# supply.net
KiCad netlist of a schematic drawn in Altium Designer
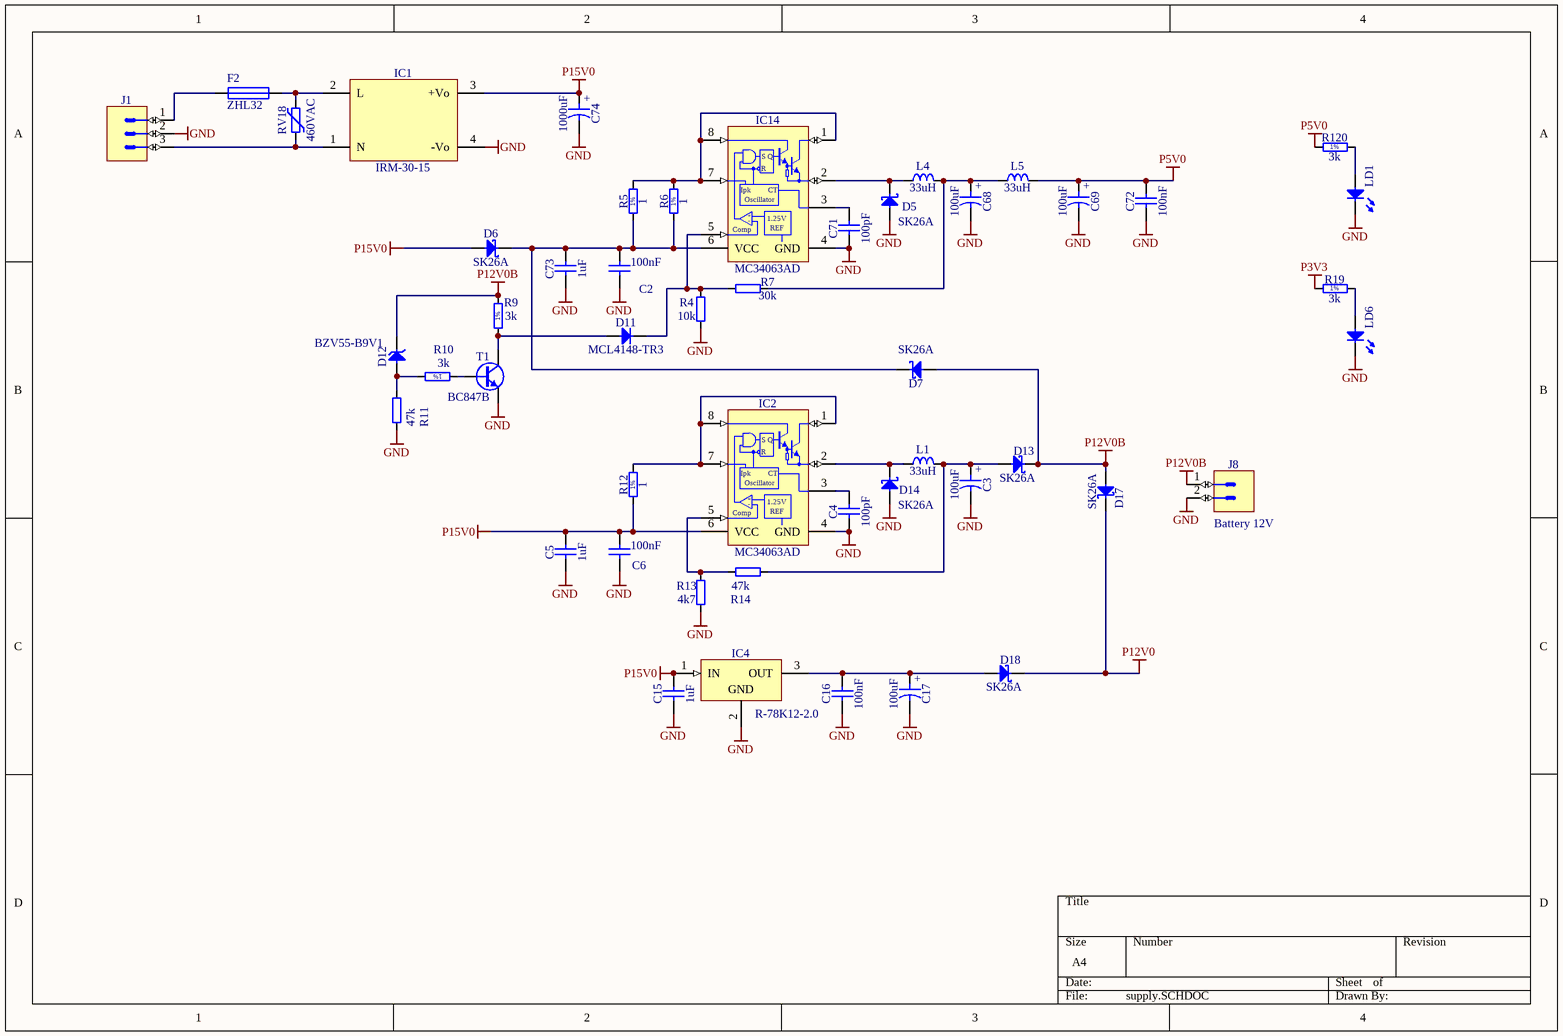
[diagram p0: supply.SCHDOC]

(export (version "E")
  (design (tool "Eeschema 10.0.6"))
  (components
    (comp (ref "C2")
      (value "100nF")
      (footprint "CAPC1608X87N")
      (description "Non-polarised capacitor")
      (fields
        (field (name "PART NUMBER") "CC0603_100NF_50V_10%_X7R")
        (field (name "VOLTAGE") "50V")
        (field (name "AUTHOR") "CERN DEM JLC")
      )
      (libsource (lib "Capacitors") (part "Capacitor - non polarized"))
    )
    (comp (ref "C3")
      (value "100uF")
      (footprint "CAPAE660X540N")
      (description "Polarised capacitor")
      (fields
        (field (name "PART NUMBER") "CAE660-540_100UF_16V_20%")
        (field (name "VOLTAGE") "16V")
        (field (name "AUTHOR") "CERN DEM JLC")
      )
      (libsource (lib "Capacitors") (part "Capacitor - polarized"))
    )
    (comp (ref "C4")
      (value "100pF")
      (footprint "CAPC1608X87N")
      (description "Non-polarised capacitor")
      (fields
        (field (name "PART NUMBER") "CC0603_100PF_50V_10%_X7R")
        (field (name "VOLTAGE") "50V")
        (field (name "AUTHOR") "CERN DEM JLC")
      )
      (libsource (lib "Capacitors") (part "Capacitor - non polarized"))
    )
    (comp (ref "C5")
      (value "1uF")
      (footprint "CAPC1608X87N")
      (description "Non-polarised capacitor")
      (fields
        (field (name "PART NUMBER") "CC0603_1UF_25V_10%_X7R")
        (field (name "VOLTAGE") "25V")
        (field (name "AUTHOR") "CERN DEM JLC")
      )
      (libsource (lib "Capacitors") (part "Capacitor - non polarized"))
    )
    (comp (ref "C6")
      (value "100nF")
      (footprint "CAPC1608X87N")
      (description "Non-polarised capacitor")
      (fields
        (field (name "PART NUMBER") "CC0603_100NF_50V_10%_X7R")
        (field (name "VOLTAGE") "50V")
        (field (name "AUTHOR") "CERN DEM JLC")
      )
      (libsource (lib "Capacitors") (part "Capacitor - non polarized"))
    )
    (comp (ref "C15")
      (value "1uF")
      (footprint "CAPC1608X87N")
      (description "Non-polarised capacitor")
      (fields
        (field (name "PART NUMBER") "CC0603_1UF_25V_10%_X7R")
        (field (name "VOLTAGE") "25V")
        (field (name "AUTHOR") "CERN DEM JLC")
      )
      (libsource (lib "Capacitors") (part "Capacitor - non polarized"))
    )
    (comp (ref "C16")
      (value "100nF")
      (footprint "CAPC1608X87N")
      (description "Non-polarised capacitor")
      (fields
        (field (name "PART NUMBER") "CC0603_100NF_50V_10%_X7R")
        (field (name "VOLTAGE") "50V")
        (field (name "AUTHOR") "CERN DEM JLC")
      )
      (libsource (lib "Capacitors") (part "Capacitor - non polarized"))
    )
    (comp (ref "C17")
      (value "100uF")
      (footprint "CAPAE660X540N")
      (description "Polarised capacitor")
      (fields
        (field (name "PART NUMBER") "CAE660-540_100UF_16V_20%")
        (field (name "VOLTAGE") "16V")
        (field (name "AUTHOR") "CERN DEM JLC")
      )
      (libsource (lib "Capacitors") (part "Capacitor - polarized"))
    )
    (comp (ref "C68")
      (value "100uF")
      (footprint "CAPAE660X540N")
      (description "Polarised capacitor")
      (fields
        (field (name "PART NUMBER") "CAE660-540_100UF_16V_20%")
        (field (name "VOLTAGE") "16V")
        (field (name "AUTHOR") "CERN DEM JLC")
      )
      (libsource (lib "Capacitors") (part "Capacitor - polarized"))
    )
    (comp (ref "C69")
      (value "100uF")
      (footprint "CAPAE660X540N")
      (description "Polarised capacitor")
      (fields
        (field (name "PART NUMBER") "CAE660-540_100UF_16V_20%")
        (field (name "VOLTAGE") "16V")
        (field (name "AUTHOR") "CERN DEM JLC")
      )
      (libsource (lib "Capacitors") (part "Capacitor - polarized"))
    )
    (comp (ref "C71")
      (value "100pF")
      (footprint "CAPC1608X87N")
      (description "Non-polarised capacitor")
      (fields
        (field (name "PART NUMBER") "CC0603_100PF_50V_10%_X7R")
        (field (name "VOLTAGE") "50V")
        (field (name "AUTHOR") "CERN DEM JLC")
      )
      (libsource (lib "Capacitors") (part "Capacitor - non polarized"))
    )
    (comp (ref "C72")
      (value "100nF")
      (footprint "CAPC1608X87N")
      (description "Non-polarised capacitor")
      (fields
        (field (name "PART NUMBER") "CC0603_100NF_50V_10%_X7R")
        (field (name "VOLTAGE") "50V")
        (field (name "AUTHOR") "CERN DEM JLC")
      )
      (libsource (lib "Capacitors") (part "Capacitor - non polarized"))
    )
    (comp (ref "C73")
      (value "1uF")
      (footprint "CAPC1608X87N")
      (description "Non-polarised capacitor")
      (fields
        (field (name "PART NUMBER") "CC0603_1UF_25V_10%_X7R")
        (field (name "VOLTAGE") "25V")
        (field (name "AUTHOR") "CERN DEM JLC")
      )
      (libsource (lib "Capacitors") (part "Capacitor - non polarized"))
    )
    (comp (ref "C74")
      (value "1000uF")
      (footprint "CAPPR500-1050X2200")
      (description "Polarised capacitor")
      (fields
        (field (name "PART NUMBER") "CAER_1000UF_25V_20%_VISHAY_MAL203856102E3")
        (field (name "VOLTAGE") "25V")
        (field (name "AUTHOR") "CERN DEM JLC")
      )
      (libsource (lib "Capacitors") (part "Capacitor - polarized"))
    )
    (comp (ref "D5")
      (value "SK26A")
      (footprint "DIOM5126X265N")
      (description "Schottky Diode")
      (fields
        (field (name "VOLTAGE") "60V")
        (field (name "POWER") "2A")
        (field (name "AUTHOR") "CERN DEM JMW")
      )
      (libsource (lib "ICs And Semiconductors") (part "Diode Schottky"))
    )
    (comp (ref "D6")
      (value "SK26A")
      (footprint "DIOM5126X265N")
      (description "Schottky Diode")
      (fields
        (field (name "VOLTAGE") "60V")
        (field (name "POWER") "2A")
        (field (name "AUTHOR") "CERN DEM JMW")
      )
      (libsource (lib "ICs And Semiconductors") (part "Diode Schottky"))
    )
    (comp (ref "D7")
      (value "SK26A")
      (footprint "DIOM5126X265N")
      (description "Schottky Diode")
      (fields
        (field (name "VOLTAGE") "60V")
        (field (name "POWER") "2A")
        (field (name "AUTHOR") "CERN DEM JMW")
      )
      (libsource (lib "ICs And Semiconductors") (part "Diode Schottky"))
    )
    (comp (ref "D11")
      (value "MCL4148-TR3")
      (footprint "DIOMELF1911N")
      (description "Diode")
      (fields
        (field (name "VOLTAGE") "75V")
        (field (name "POWER") "200mA")
        (field (name "AUTHOR") "CERN DEM JLC")
      )
      (libsource (lib "ICs And Semiconductors") (part "Diode"))
    )
    (comp (ref "D12")
      (value "BZV55-B9V1")
      (footprint "DIOMELF3515N")
      (description "Zener Diode")
      (fields
        (field (name "VOLTAGE") "9V1")
        (field (name "POWER") "500mW")
        (field (name "AUTHOR") "CERN DEM JLC")
      )
      (libsource (lib "ICs And Semiconductors") (part "Diode Zener"))
    )
    (comp (ref "D13")
      (value "SK26A")
      (footprint "DIOM5126X265N")
      (description "Schottky Diode")
      (fields
        (field (name "VOLTAGE") "60V")
        (field (name "POWER") "2A")
        (field (name "AUTHOR") "CERN DEM JMW")
      )
      (libsource (lib "ICs And Semiconductors") (part "Diode Schottky"))
    )
    (comp (ref "D14")
      (value "SK26A")
      (footprint "DIOM5126X265N")
      (description "Schottky Diode")
      (fields
        (field (name "VOLTAGE") "60V")
        (field (name "POWER") "2A")
        (field (name "AUTHOR") "CERN DEM JMW")
      )
      (libsource (lib "ICs And Semiconductors") (part "Diode Schottky"))
    )
    (comp (ref "D17")
      (value "SK26A")
      (footprint "DIOM5126X265N")
      (description "Schottky Diode")
      (fields
        (field (name "VOLTAGE") "60V")
        (field (name "POWER") "2A")
        (field (name "AUTHOR") "CERN DEM JMW")
      )
      (libsource (lib "ICs And Semiconductors") (part "Diode Schottky"))
    )
    (comp (ref "D18")
      (value "SK26A")
      (footprint "DIOM5126X265N")
      (description "Schottky Diode")
      (fields
        (field (name "VOLTAGE") "60V")
        (field (name "POWER") "2A")
        (field (name "AUTHOR") "CERN DEM JMW")
      )
      (libsource (lib "ICs And Semiconductors") (part "Diode Schottky"))
    )
    (comp (ref "F2")
      (value "ZHL32")
      (footprint "library:fuse_ZHL32")
      (description "Fuse")
      (libsource (lib "LIBRARY_SCH") (part "FUSE"))
    )
    (comp (ref "IC1")
      (value "IRM-30-15")
      (footprint "library-modules:PWS_MEANWELL_IRM-30")
      (description "Power Supply")
      (fields (field (name "MANUFACTURER") "MEAN WELL") (field (name "AUTHOR") "GK"))
      (libsource (lib "Regulators_SMPS") (part "AC_DC_IRM-30-15"))
    )
    (comp (ref "IC2")
      (value "MC34063AD")
      (footprint "SOIC127P600X175-8N")
      (description "3V to 40V 1.5A Peak Boost/Buck/Inverting Switching Regulator")
      (fields (field (name "MANUFACTURER") "TEXAS INSTRUMENTS") (field (name "AUTHOR") "CERN DEM JLC"))
      (libsource (lib "ICs And Semiconductors") (part "MC34063A"))
    )
    (comp (ref "IC4")
      (value "R-78K12-2.0")
      (footprint "DCDC_RECOM_R-78C")
      (description "15-42VDC to 12VDC, Iout (max) 1A, DC-DC Converter")
      (fields (field (name "MANUFACTURER") "RECOM") (field (name "AUTHOR") "CERN DEM BC"))
      (libsource (lib "ICs And Semiconductors") (part "DCDC_RECOM_R-78C"))
    )
    (comp (ref "IC14")
      (value "MC34063AD")
      (footprint "SOIC127P600X175-8N")
      (description "3V to 40V 1.5A Peak Boost/Buck/Inverting Switching Regulator")
      (fields (field (name "MANUFACTURER") "TEXAS INSTRUMENTS") (field (name "AUTHOR") "CERN DEM JLC"))
      (libsource (lib "ICs And Semiconductors") (part "MC34063A"))
    )
    (comp (ref "J1")
      (value "~")
      (footprint "PHOENIX_1757255")
      (description "Connector 3 Male")
      (fields
        (field (name "PART NUMBER") "PHOENIX_1757255")
        (field (name "MANUFACTURER") "PHOENIX CONTACT")
        (field (name "AUTHOR") "CERN DEM JLC")
      )
      (libsource (lib "Connectors") (part "Connector 3 Male"))
    )
    (comp (ref "J8")
      (value "~")
      (footprint "PHOENIX_1803277")
      (description "Connector 2 Male")
      (fields
        (field (name "PART NUMBER") "PHOENIX_1803277")
        (field (name "MANUFACTURER") "PHOENIX CONTACT")
        (field (name "AUTHOR") "CERN DEM JLC")
      )
      (libsource (lib "Connectors") (part "Connector 2 Male"))
    )
    (comp (ref "L1")
      (value "33uH")
      (footprint "IND_BOURNS_SRP1038A")
      (description "Inductor")
      (fields
        (field (name "PART NUMBER") "IND_33UH_20%_BOURNS_SRP1038A")
        (field (name "POWER") "3.5A")
        (field (name "AUTHOR") "CERN DEM HF")
      )
      (libsource (lib "Inductors & Transformers") (part "Inductor"))
    )
    (comp (ref "L4")
      (value "33uH")
      (footprint "IND_BOURNS_SRP1038A")
      (description "Inductor")
      (fields
        (field (name "PART NUMBER") "IND_33UH_20%_BOURNS_SRP1038A")
        (field (name "POWER") "3.5A")
        (field (name "AUTHOR") "CERN DEM HF")
      )
      (libsource (lib "Inductors & Transformers") (part "Inductor"))
    )
    (comp (ref "L5")
      (value "33uH")
      (footprint "IND_BOURNS_SRP1038A")
      (description "Inductor")
      (fields
        (field (name "PART NUMBER") "IND_33UH_20%_BOURNS_SRP1038A")
        (field (name "POWER") "3.5A")
        (field (name "AUTHOR") "CERN DEM HF")
      )
      (libsource (lib "Inductors & Transformers") (part "Inductor"))
    )
    (comp (ref "LD1")
      (value "Green")
      (footprint "LED_KINGBRIGHT_KP-1608CGCK")
      (description "LED Green 1C 2A")
      (fields
        (field (name "PART NUMBER") "LED_KINGBRIGHT_KP-1608CGCK")
        (field (name "MANUFACTURER") "KINGBRIGHT")
        (field (name "AUTHOR") "CERN DEM HF")
      )
      (libsource (lib "ICs And Semiconductors") (part "LED Green 1C 2A"))
    )
    (comp (ref "LD6")
      (value "Green")
      (footprint "LED_KINGBRIGHT_KP-1608CGCK")
      (description "LED Green 1C 2A")
      (fields
        (field (name "PART NUMBER") "LED_KINGBRIGHT_KP-1608CGCK")
        (field (name "MANUFACTURER") "KINGBRIGHT")
        (field (name "AUTHOR") "CERN DEM HF")
      )
      (libsource (lib "ICs And Semiconductors") (part "LED Green 1C 2A"))
    )
    (comp (ref "R4")
      (value "10k")
      (footprint "RESC1608X55N")
      (description "Resistor - 1%")
      (fields
        (field (name "PART NUMBER") "R0603_10K_1%_0.1W_100PPM")
        (field (name "POWER") "0.1W")
        (field (name "AUTHOR") "CERN DEM JLC")
      )
      (libsource (lib "Resistors") (part "Resistor - 1%"))
    )
    (comp (ref "R5")
      (value "1")
      (footprint "RESC1608X55N")
      (description "Resistor - 1%")
      (fields
        (field (name "PART NUMBER") "R0603_1R_1%_0.1W_200PPM")
        (field (name "POWER") "0.1W")
        (field (name "AUTHOR") "CERN DEM JLC")
      )
      (libsource (lib "Resistors") (part "Resistor - 1%"))
    )
    (comp (ref "R6")
      (value "1")
      (footprint "RESC1608X55N")
      (description "Resistor - 1%")
      (fields
        (field (name "PART NUMBER") "R0603_1R_1%_0.1W_200PPM")
        (field (name "POWER") "0.1W")
        (field (name "AUTHOR") "CERN DEM JLC")
      )
      (libsource (lib "Resistors") (part "Resistor - 1%"))
    )
    (comp (ref "R7")
      (value "30k")
      (footprint "RESC1608X55N")
      (description "Resistor - 1%")
      (fields
        (field (name "PART NUMBER") "R0603_30K_1%_0.1W_100PPM")
        (field (name "POWER") "0.1W")
        (field (name "AUTHOR") "CERN DEM JLC")
      )
      (libsource (lib "Resistors") (part "Resistor - 1%"))
    )
    (comp (ref "R9")
      (value "3k")
      (footprint "RESC1608X55N")
      (description "Resistor - 1%")
      (fields
        (field (name "PART NUMBER") "R0603_3K_1%_0.1W_100PPM")
        (field (name "POWER") "0.1W")
        (field (name "AUTHOR") "CERN DEM JLC")
      )
      (libsource (lib "Resistors") (part "Resistor - 1%"))
    )
    (comp (ref "R10")
      (value "3k")
      (footprint "RESC1608X55N")
      (description "Resistor - 1%")
      (fields
        (field (name "PART NUMBER") "R0603_3K_1%_0.1W_100PPM")
        (field (name "POWER") "0.1W")
        (field (name "AUTHOR") "CERN DEM JLC")
      )
      (libsource (lib "Resistors") (part "Resistor - 1%"))
    )
    (comp (ref "R11")
      (value "47k")
      (footprint "RESC1608X55N")
      (description "Resistor - 1%")
      (fields
        (field (name "PART NUMBER") "R0603_47K_1%_0.1W_100PPM")
        (field (name "POWER") "0.1W")
        (field (name "AUTHOR") "CERN DEM JLC")
      )
      (libsource (lib "Resistors") (part "Resistor - 1%"))
    )
    (comp (ref "R12")
      (value "1")
      (footprint "RESC1608X55N")
      (description "Resistor - 1%")
      (fields
        (field (name "PART NUMBER") "R0603_1R_1%_0.1W_200PPM")
        (field (name "POWER") "0.1W")
        (field (name "AUTHOR") "CERN DEM JLC")
      )
      (libsource (lib "Resistors") (part "Resistor - 1%"))
    )
    (comp (ref "R13")
      (value "4k7")
      (footprint "RESC1608X55N")
      (description "Resistor - 1%")
      (fields
        (field (name "PART NUMBER") "R0603_4K7_1%_0.1W_100PPM")
        (field (name "POWER") "0.1W")
        (field (name "AUTHOR") "CERN DEM JLC")
      )
      (libsource (lib "Resistors") (part "Resistor - 1%"))
    )
    (comp (ref "R14")
      (value "47k")
      (footprint "RESC1608X55N")
      (description "Resistor - 1%")
      (fields
        (field (name "PART NUMBER") "R0603_47K_1%_0.1W_100PPM")
        (field (name "POWER") "0.1W")
        (field (name "AUTHOR") "CERN DEM JLC")
      )
      (libsource (lib "Resistors") (part "Resistor - 1%"))
    )
    (comp (ref "R19")
      (value "3k")
      (footprint "RESC1608X55N")
      (description "Resistor - 1%")
      (fields
        (field (name "PART NUMBER") "R0603_3K_1%_0.1W_100PPM")
        (field (name "POWER") "0.1W")
        (field (name "AUTHOR") "CERN DEM JLC")
      )
      (libsource (lib "Resistors") (part "Resistor - 1%"))
    )
    (comp (ref "R120")
      (value "3k")
      (footprint "RESC1608X55N")
      (description "Resistor - 1%")
      (fields
        (field (name "PART NUMBER") "R0603_3K_1%_0.1W_100PPM")
        (field (name "POWER") "0.1W")
        (field (name "AUTHOR") "CERN DEM JLC")
      )
      (libsource (lib "Resistors") (part "Resistor - 1%"))
    )
    (comp (ref "RV18")
      (value "460VAC")
      (footprint "VAR_EPCOS_B72210S0461K101")
      (description "Varistor")
      (fields
        (field (name "PART NUMBER") "VAR_EPCOS_B72210S0461K101")
        (field (name "POWER") "0.4W")
        (field (name "AUTHOR") "CERN DEM JLC")
      )
      (libsource (lib "Resistors") (part "Varistor"))
    )
    (comp (ref "T1")
      (value "BC847B")
      (footprint "SOT95P230X110-3N")
      (description "NPN Transistor")
      (fields (field (name "MANUFACTURER") "NXP SEMICONDUCTORS") (field (name "AUTHOR") "CERN DEM JLC"))
      (libsource (lib "ICs And Semiconductors") (part "NPN B1 E2 C3"))
    )
  )
  (nets
    (net (code "1") (name "GND") (class "Default")
      (node (ref "C15") (pin "1") (pinfunction "1_1") (pintype "passive"))
      (node (ref "C16") (pin "1") (pinfunction "1_1") (pintype "passive"))
      (node (ref "C17") (pin "2") (pinfunction "2_2") (pintype "passive"))
      (node (ref "C2") (pin "1") (pinfunction "1_1") (pintype "passive"))
      (node (ref "C3") (pin "2") (pinfunction "2_2") (pintype "passive"))
      (node (ref "C4") (pin "1") (pinfunction "1_1") (pintype "passive"))
      (node (ref "C5") (pin "1") (pinfunction "1_1") (pintype "passive"))
      (node (ref "C6") (pin "1") (pinfunction "1_1") (pintype "passive"))
      (node (ref "C68") (pin "2") (pinfunction "2_2") (pintype "passive"))
      (node (ref "C69") (pin "2") (pinfunction "2_2") (pintype "passive"))
      (node (ref "C71") (pin "1") (pinfunction "1_1") (pintype "passive"))
      (node (ref "C72") (pin "1") (pinfunction "1_1") (pintype "passive"))
      (node (ref "C73") (pin "1") (pinfunction "1_1") (pintype "passive"))
      (node (ref "C74") (pin "2") (pinfunction "2_2") (pintype "passive"))
      (node (ref "D14") (pin "2") (pinfunction "A_2") (pintype "passive"))
      (node (ref "D5") (pin "2") (pinfunction "A_2") (pintype "passive"))
      (node (ref "IC1") (pin "4") (pinfunction "-Vo_4") (pintype "power_in"))
      (node (ref "IC14") (pin "4") (pinfunction "GND_4") (pintype "power_in"))
      (node (ref "IC2") (pin "4") (pinfunction "GND_4") (pintype "power_in"))
      (node (ref "IC4") (pin "2") (pinfunction "GND_2") (pintype "power_in"))
      (node (ref "J1") (pin "2") (pinfunction "2_2") (pintype "bidirectional"))
      (node (ref "J8") (pin "2") (pinfunction "2_2") (pintype "bidirectional"))
      (node (ref "LD1") (pin "1") (pinfunction "C_1") (pintype "passive"))
      (node (ref "LD6") (pin "1") (pinfunction "C_1") (pintype "passive"))
      (node (ref "R11") (pin "1") (pinfunction "1_1") (pintype "passive"))
      (node (ref "R13") (pin "1") (pinfunction "1_1") (pintype "passive"))
      (node (ref "R4") (pin "1") (pinfunction "1_1") (pintype "passive"))
      (node (ref "T1") (pin "2") (pinfunction "E_2") (pintype "passive"))
    )
    (net (code "2") (name "Net-(C68-Pad1)") (class "Default")
      (node (ref "C68") (pin "1") (pinfunction "1_1") (pintype "passive"))
      (node (ref "L4") (pin "2") (pinfunction "2_2") (pintype "passive"))
      (node (ref "L5") (pin "1") (pinfunction "1_1") (pintype "passive"))
      (node (ref "R7") (pin "2") (pinfunction "2_2") (pintype "passive"))
    )
    (net (code "3") (name "Net-(D5-C)") (class "Default")
      (node (ref "D5") (pin "1") (pinfunction "C_1") (pintype "passive"))
      (node (ref "IC14") (pin "2") (pinfunction "SWE_2") (pintype "bidirectional"))
      (node (ref "L4") (pin "1") (pinfunction "1_1") (pintype "passive"))
    )
    (net (code "4") (name "Net-(D6-C)") (class "Default")
      (node (ref "C2") (pin "2") (pinfunction "2_2") (pintype "passive"))
      (node (ref "C73") (pin "2") (pinfunction "2_2") (pintype "passive"))
      (node (ref "D6") (pin "1") (pinfunction "C_1") (pintype "passive"))
      (node (ref "D7") (pin "1") (pinfunction "C_1") (pintype "passive"))
      (node (ref "IC14") (pin "6") (pinfunction "VCC_6") (pintype "power_in"))
      (node (ref "R5") (pin "1") (pinfunction "1_1") (pintype "passive"))
      (node (ref "R6") (pin "1") (pinfunction "1_1") (pintype "passive"))
    )
    (net (code "5") (name "Net-(D11-A)") (class "Default")
      (node (ref "D11") (pin "2") (pinfunction "A_2") (pintype "passive"))
      (node (ref "R9") (pin "1") (pinfunction "1_1") (pintype "passive"))
      (node (ref "T1") (pin "3") (pinfunction "C_3") (pintype "passive"))
    )
    (net (code "6") (name "Net-(D11-C)") (class "Default")
      (node (ref "D11") (pin "1") (pinfunction "C_1") (pintype "passive"))
      (node (ref "IC14") (pin "5") (pinfunction "COMP_5") (pintype "input"))
      (node (ref "R4") (pin "2") (pinfunction "2_2") (pintype "passive"))
      (node (ref "R7") (pin "1") (pinfunction "1_1") (pintype "passive"))
    )
    (net (code "7") (name "Net-(D12-A)") (class "Default")
      (node (ref "D12") (pin "2") (pinfunction "A_2") (pintype "passive"))
      (node (ref "R10") (pin "2") (pinfunction "2_2") (pintype "passive"))
      (node (ref "R11") (pin "2") (pinfunction "2_2") (pintype "passive"))
    )
    (net (code "8") (name "Net-(D13-A)") (class "Default")
      (node (ref "C3") (pin "1") (pinfunction "1_1") (pintype "passive"))
      (node (ref "D13") (pin "2") (pinfunction "A_2") (pintype "passive"))
      (node (ref "L1") (pin "2") (pinfunction "2_2") (pintype "passive"))
      (node (ref "R14") (pin "2") (pinfunction "2_2") (pintype "passive"))
    )
    (net (code "9") (name "Net-(D14-C)") (class "Default")
      (node (ref "D14") (pin "1") (pinfunction "C_1") (pintype "passive"))
      (node (ref "IC2") (pin "2") (pinfunction "SWE_2") (pintype "bidirectional"))
      (node (ref "L1") (pin "1") (pinfunction "1_1") (pintype "passive"))
    )
    (net (code "10") (name "Net-(D18-A)") (class "Default")
      (node (ref "C16") (pin "2") (pinfunction "2_2") (pintype "passive"))
      (node (ref "C17") (pin "1") (pinfunction "1_1") (pintype "passive"))
      (node (ref "D18") (pin "2") (pinfunction "A_2") (pintype "passive"))
      (node (ref "IC4") (pin "3") (pinfunction "OUT_3") (pintype "power_in"))
    )
    (net (code "11") (name "Net-(F2-Pad1)") (class "Default")
      (node (ref "F2") (pin "1") (pinfunction "1_1") (pintype "passive"))
      (node (ref "J1") (pin "1") (pinfunction "1_1") (pintype "bidirectional"))
    )
    (net (code "12") (name "Net-(IC1-L)") (class "Default")
      (node (ref "F2") (pin "2") (pinfunction "2_2") (pintype "passive"))
      (node (ref "IC1") (pin "2") (pinfunction "L_2") (pintype "power_in"))
      (node (ref "RV18") (pin "2") (pinfunction "2_2") (pintype "passive"))
    )
    (net (code "13") (name "Net-(IC1-N)") (class "Default")
      (node (ref "IC1") (pin "1") (pinfunction "N_1") (pintype "power_in"))
      (node (ref "J1") (pin "3") (pinfunction "3_3") (pintype "bidirectional"))
      (node (ref "RV18") (pin "1") (pinfunction "1_1") (pintype "passive"))
    )
    (net (code "14") (name "Net-(IC2-COMP)") (class "Default")
      (node (ref "IC2") (pin "5") (pinfunction "COMP_5") (pintype "input"))
      (node (ref "R13") (pin "2") (pinfunction "2_2") (pintype "passive"))
      (node (ref "R14") (pin "1") (pinfunction "1_1") (pintype "passive"))
    )
    (net (code "15") (name "Net-(IC2-DRVC)") (class "Default")
      (node (ref "IC2") (pin "1") (pinfunction "SWC_1") (pintype "bidirectional"))
      (node (ref "IC2") (pin "7") (pinfunction "Ipk_7") (pintype "input"))
      (node (ref "IC2") (pin "8") (pinfunction "DRVC_8") (pintype "input"))
      (node (ref "R12") (pin "2") (pinfunction "2_2") (pintype "passive"))
    )
    (net (code "16") (name "Net-(IC2-TC)") (class "Default")
      (node (ref "C4") (pin "2") (pinfunction "2_2") (pintype "passive"))
      (node (ref "IC2") (pin "3") (pinfunction "TC_3") (pintype "passive"))
    )
    (net (code "17") (name "Net-(IC14-DRVC)") (class "Default")
      (node (ref "IC14") (pin "1") (pinfunction "SWC_1") (pintype "bidirectional"))
      (node (ref "IC14") (pin "7") (pinfunction "Ipk_7") (pintype "input"))
      (node (ref "IC14") (pin "8") (pinfunction "DRVC_8") (pintype "input"))
      (node (ref "R5") (pin "2") (pinfunction "2_2") (pintype "passive"))
      (node (ref "R6") (pin "2") (pinfunction "2_2") (pintype "passive"))
    )
    (net (code "18") (name "Net-(IC14-TC)") (class "Default")
      (node (ref "C71") (pin "2") (pinfunction "2_2") (pintype "passive"))
      (node (ref "IC14") (pin "3") (pinfunction "TC_3") (pintype "passive"))
    )
    (net (code "19") (name "Net-(LD1-A)") (class "Default")
      (node (ref "LD1") (pin "2") (pinfunction "A_2") (pintype "passive"))
      (node (ref "R120") (pin "2") (pinfunction "2_2") (pintype "passive"))
    )
    (net (code "20") (name "Net-(LD6-A)") (class "Default")
      (node (ref "LD6") (pin "2") (pinfunction "A_2") (pintype "passive"))
      (node (ref "R19") (pin "2") (pinfunction "2_2") (pintype "passive"))
    )
    (net (code "21") (name "Net-(T1-B)") (class "Default")
      (node (ref "R10") (pin "1") (pinfunction "1_1") (pintype "passive"))
      (node (ref "T1") (pin "1") (pinfunction "B_1") (pintype "passive"))
    )
    (net (code "22") (name "P3V3") (class "Default")
      (node (ref "R19") (pin "1") (pinfunction "1_1") (pintype "passive"))
    )
    (net (code "23") (name "P5V0") (class "Default")
      (node (ref "C69") (pin "1") (pinfunction "1_1") (pintype "passive"))
      (node (ref "C72") (pin "2") (pinfunction "2_2") (pintype "passive"))
      (node (ref "L5") (pin "2") (pinfunction "2_2") (pintype "passive"))
      (node (ref "R120") (pin "1") (pinfunction "1_1") (pintype "passive"))
    )
    (net (code "24") (name "P12V0") (class "Default")
      (node (ref "D17") (pin "1") (pinfunction "C_1") (pintype "passive"))
      (node (ref "D18") (pin "1") (pinfunction "C_1") (pintype "passive"))
    )
    (net (code "25") (name "P12V0B") (class "Default")
      (node (ref "D12") (pin "1") (pinfunction "C_1") (pintype "passive"))
      (node (ref "D13") (pin "1") (pinfunction "C_1") (pintype "passive"))
      (node (ref "D17") (pin "2") (pinfunction "A_2") (pintype "passive"))
      (node (ref "D7") (pin "2") (pinfunction "A_2") (pintype "passive"))
      (node (ref "J8") (pin "1") (pinfunction "1_1") (pintype "bidirectional"))
      (node (ref "R9") (pin "2") (pinfunction "2_2") (pintype "passive"))
    )
    (net (code "26") (name "P15V0") (class "Default")
      (node (ref "C15") (pin "2") (pinfunction "2_2") (pintype "passive"))
      (node (ref "C5") (pin "2") (pinfunction "2_2") (pintype "passive"))
      (node (ref "C6") (pin "2") (pinfunction "2_2") (pintype "passive"))
      (node (ref "C74") (pin "1") (pinfunction "1_1") (pintype "passive"))
      (node (ref "D6") (pin "2") (pinfunction "A_2") (pintype "passive"))
      (node (ref "IC1") (pin "3") (pinfunction "+Vo_3") (pintype "power_in"))
      (node (ref "IC2") (pin "6") (pinfunction "VCC_6") (pintype "power_in"))
      (node (ref "IC4") (pin "1") (pinfunction "IN_1") (pintype "input"))
      (node (ref "R12") (pin "1") (pinfunction "1_1") (pintype "passive"))
    )
  )
)
